# Controller_Schematic.net
KiCad netlist of a schematic drawn in Altium Designer
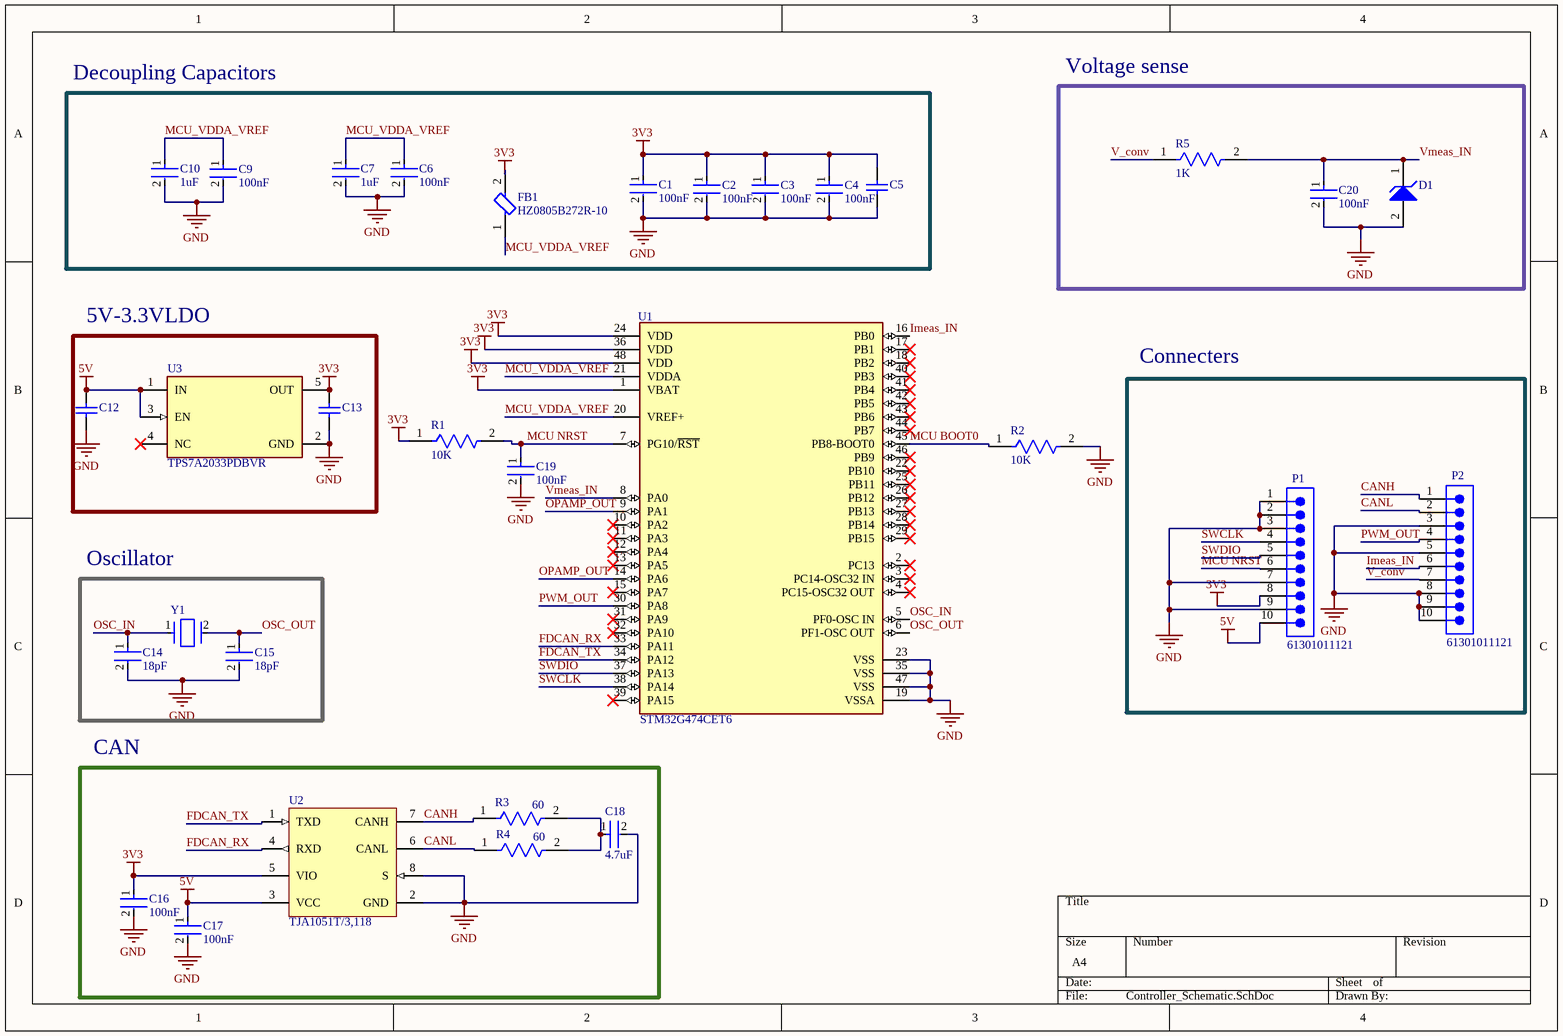
[diagram p0: Controller_Schematic.SchDoc]

(export (version "E")
  (design (tool "Eeschema 10.0.6"))
  (components
    (comp (ref "C1")
      (value "100nF")
      (footprint "FP-GCM21B-0_15-MFG")
      (description "Ceramic Capacitor for Automotive 100nF ±10% 100VDC X7R 0805 Embossed T/R")
      (fields (field (name "TOLERANCE") "10%") (field (name "VOLTAGE") "100V"))
      (libsource (lib "Altium Content Vault") (part "02cd4be3c70576c341d710602a673aa"))
    )
    (comp (ref "C2")
      (value "100nF")
      (footprint "FP-GCM21B-0_15-MFG")
      (description "Ceramic Capacitor for Automotive 100nF ±10% 100VDC X7R 0805 Embossed T/R")
      (fields (field (name "TOLERANCE") "10%") (field (name "VOLTAGE") "100V"))
      (libsource (lib "Altium Content Vault") (part "02cd4be3c70576c341d710602a673aa"))
    )
    (comp (ref "C3")
      (value "100nF")
      (footprint "FP-GCM21B-0_15-MFG")
      (description "Ceramic Capacitor for Automotive 100nF ±10% 100VDC X7R 0805 Embossed T/R")
      (fields (field (name "TOLERANCE") "10%") (field (name "VOLTAGE") "100V"))
      (libsource (lib "Altium Content Vault") (part "02cd4be3c70576c341d710602a673aa"))
    )
    (comp (ref "C4")
      (value "100nF")
      (footprint "FP-GCM21B-0_15-MFG")
      (description "Ceramic Capacitor for Automotive 100nF ±10% 100VDC X7R 0805 Embossed T/R")
      (fields (field (name "TOLERANCE") "10%") (field (name "VOLTAGE") "100V"))
      (libsource (lib "Altium Content Vault") (part "02cd4be3c70576c341d710602a673aa"))
    )
    (comp (ref "C5")
      (value "GRM21BR61A475KA73L")
      (footprint "CAPC2013X140X45NL15T25")
      (fields (field (name "MANUFACTURER") "Murata"))
      (libsource (lib "Altium Content Vault") (part "CAP"))
    )
    (comp (ref "C6")
      (value "100nF")
      (footprint "FP-GCM21B-0_15-MFG")
      (description "Ceramic Capacitor for Automotive 100nF ±10% 100VDC X7R 0805 Embossed T/R")
      (fields (field (name "TOLERANCE") "10%") (field (name "VOLTAGE") "100V"))
      (libsource (lib "Altium Content Vault") (part "02cd4be3c70576c341d710602a673aa"))
    )
    (comp (ref "C7")
      (value "1uF")
      (footprint "FP-GCM21B-0_15-MFG")
      (description "Ceramic Capacitor for Automotive 1uF ±10% 25VDC X7R 0805 Embossed T/R")
      (fields (field (name "TOLERANCE") "10%") (field (name "VOLTAGE") "25V"))
      (libsource (lib "Altium Content Vault") (part "02cd4be3c70576c341d710602a673aa"))
    )
    (comp (ref "C9")
      (value "100nF")
      (footprint "FP-GCM21B-0_15-MFG")
      (description "Ceramic Capacitor for Automotive 100nF ±10% 100VDC X7R 0805 Embossed T/R")
      (fields (field (name "TOLERANCE") "10%") (field (name "VOLTAGE") "100V"))
      (libsource (lib "Altium Content Vault") (part "02cd4be3c70576c341d710602a673aa"))
    )
    (comp (ref "C10")
      (value "1uF")
      (footprint "FP-GCM21B-0_15-MFG")
      (description "Ceramic Capacitor for Automotive 1uF ±10% 25VDC X7R 0805 Embossed T/R")
      (fields (field (name "TOLERANCE") "10%") (field (name "VOLTAGE") "25V"))
      (libsource (lib "Altium Content Vault") (part "02cd4be3c70576c341d710602a673aa"))
    )
    (comp (ref "C12")
      (value "GRM21BR61A106KE19L")
      (footprint "MURA-0805_H_1.35_M")
      (description "CAP, Ceramic, 10 uF, 10%, 10 V, 0805, RoHS, Tape and Reel")
      (fields (field (name "MANUFACTURER") "Murata") (field (name "TOLERANCE") "±10%"))
      (libsource (lib "Altium Content Vault") (part "CAP-NP-2"))
    )
    (comp (ref "C13")
      (value "GRM21BR61A106KE19L")
      (footprint "MURA-0805_H_1.35_M")
      (description "CAP, Ceramic, 10 uF, 10%, 10 V, 0805, RoHS, Tape and Reel")
      (fields (field (name "MANUFACTURER") "Murata") (field (name "TOLERANCE") "±10%"))
      (libsource (lib "Altium Content Vault") (part "CAP-NP-2"))
    )
    (comp (ref "C14")
      (value "18pF")
      (footprint "FP-GRM21A-0_2-IPC_B")
      (description "Chip Multilayer Ceramic Capacitors for General Purpose, 0805, 18pF, C0G, 30ppm/°C, 5%, 200V")
      (fields (field (name "VOLTAGE") "200V") (field (name "TOLERANCE") "5%"))
      (libsource (lib "Altium Content Vault") (part "02cd4be3c70576c341d710602a673aa"))
    )
    (comp (ref "C15")
      (value "18pF")
      (footprint "FP-GRM21A-0_2-IPC_B")
      (description "Chip Multilayer Ceramic Capacitors for General Purpose, 0805, 18pF, C0G, 30ppm/°C, 5%, 200V")
      (fields (field (name "VOLTAGE") "200V") (field (name "TOLERANCE") "5%"))
      (libsource (lib "Altium Content Vault") (part "02cd4be3c70576c341d710602a673aa"))
    )
    (comp (ref "C16")
      (value "100nF")
      (footprint "FP-GCM21B-0_15-MFG")
      (description "Ceramic Capacitor for Automotive 100nF ±10% 100VDC X7R 0805 Embossed T/R")
      (fields (field (name "TOLERANCE") "10%") (field (name "VOLTAGE") "100V"))
      (libsource (lib "Altium Content Vault") (part "02cd4be3c70576c341d710602a673aa"))
    )
    (comp (ref "C17")
      (value "100nF")
      (footprint "FP-GCM21B-0_15-MFG")
      (description "Ceramic Capacitor for Automotive 100nF ±10% 100VDC X7R 0805 Embossed T/R")
      (fields (field (name "TOLERANCE") "10%") (field (name "VOLTAGE") "100V"))
      (libsource (lib "Altium Content Vault") (part "02cd4be3c70576c341d710602a673aa"))
    )
    (comp (ref "C18")
      (value "4.7uF")
      (footprint "FP-GCM21B-0_2-e0_3_0_75-IPC_C")
      (description "Ceramic Capacitor for Automotive 4.7nF ±1% 250VDC C0G 0805 Embossed T/R")
      (libsource (lib "Altium Content Vault") (part "11868f565c42a9108669ba33697ecf6"))
    )
    (comp (ref "C19")
      (value "100nF")
      (footprint "FP-GCM21B-0_15-MFG")
      (description "Ceramic Capacitor for Automotive 100nF ±10% 100VDC X7R 0805 Embossed T/R")
      (fields (field (name "TOLERANCE") "10%") (field (name "VOLTAGE") "100V"))
      (libsource (lib "Altium Content Vault") (part "02cd4be3c70576c341d710602a673aa"))
    )
    (comp (ref "C20")
      (value "100nF")
      (footprint "FP-GCM21B-0_15-MFG")
      (description "Ceramic Capacitor for Automotive 100nF ±10% 100VDC X7R 0805 Embossed T/R")
      (fields (field (name "TOLERANCE") "10%") (field (name "VOLTAGE") "100V"))
      (libsource (lib "Altium Content Vault") (part "02cd4be3c70576c341d710602a673aa"))
    )
    (comp (ref "D1")
      (value "MMSZ5226CT1G")
      (footprint "ONSC-SOD-123-2-425-04_V")
      (description "Zener Voltage Regulator, 500 mW, 2-Pin SOD-123, Pb-Free, Tape and Reel")
      (fields (field (name "MANUFACTURER") "On Semiconductor"))
      (libsource (lib "Altium Content Vault") (part "ONSC-K1A2-2"))
    )
    (comp (ref "FB1")
      (value "HZ0805B272R-10")
      (footprint "FP-HZ0805B272R-10-MFG")
      (description "FERRITE BEAD 2.7 KOHM 0805 1LN")
      (libsource (lib "Altium Content Vault") (part "5f30dd21d616792df468990f7003faa"))
    )
    (comp (ref "P1")
      (value "61301011121")
      (footprint "61301011121")
      (description "THT Vertical Pin Header WR-PHD, Pitch 2.54 mm, Single Row, 10 pins")
      (libsource (lib "Altium Content Vault") (part "Header_Male_1R_10P"))
    )
    (comp (ref "P2")
      (value "61301011121")
      (footprint "61301011121")
      (description "THT Vertical Pin Header WR-PHD, Pitch 2.54 mm, Single Row, 10 pins")
      (libsource (lib "Altium Content Vault") (part "Header_Male_1R_10P"))
    )
    (comp (ref "R1")
      (value "10K")
      (footprint "FP-SR0805-MFG")
      (description "RES SMD 0805 1/2W 1% 10K OHM")
      (fields (field (name "MANUFACTURER PART NUMBER") "SR0805FR-4710KL") (field (name "TOLERANCE") "0.01"))
      (libsource (lib "Altium Content Vault") (part "1029c3af85768c4190bb7ad29bc67b5"))
    )
    (comp (ref "R2")
      (value "10K")
      (footprint "FP-SR0805-MFG")
      (description "RES SMD 0805 1/2W 1% 10K OHM")
      (fields (field (name "MANUFACTURER PART NUMBER") "SR0805FR-4710KL") (field (name "TOLERANCE") "0.01"))
      (libsource (lib "Altium Content Vault") (part "1029c3af85768c4190bb7ad29bc67b5"))
    )
    (comp (ref "R3")
      (value "60")
      (footprint "FP-AC0805-MFG")
      (fields
        (field (name "MANUFACTURER") "Yageo")
        (field (name "OCTOPART") "https://octopart.com/ac0805fr-0759rl-yageo-91867354")
        (field (name "MANUFACTURER PART NUMBER") "AC0805FR-0759RL")
      )
      (libsource (lib "Altium Content Vault") (part "1029c3af85768c4190bb7ad29bc67b5"))
    )
    (comp (ref "R4")
      (value "60")
      (footprint "FP-AC0805-MFG")
      (fields
        (field (name "MANUFACTURER") "Yageo")
        (field (name "OCTOPART") "https://octopart.com/ac0805fr-0759rl-yageo-91867354")
        (field (name "MANUFACTURER PART NUMBER") "AC0805FR-0759RL")
      )
      (libsource (lib "Altium Content Vault") (part "1029c3af85768c4190bb7ad29bc67b5"))
    )
    (comp (ref "R5")
      (value "1K")
      (footprint "FP-AT0805-IPC_B")
      (description "Thin Film Chip Resistors Automotive Grade 1kΩ 0.5% 50ppm/°C 0805")
      (fields (field (name "TOLERANCE") "0.5%"))
      (libsource (lib "Altium Content Vault") (part "1029c3af85768c4190bb7ad29bc67b5"))
    )
    (comp (ref "U1")
      (value "STM32G474CET6")
      (footprint "FP-STM32G474CET6-MFG")
      (description "MAINSTREAM ARM CORTEX-M4 CORE WI")
      (fields
        (field (name "OCTOPART") "https://octopart.com/stm32g474cet6-stmicroelectronics-99072248")
        (field (name "MANUFACTURER") "STMicroelectronics")
      )
      (libsource (lib "Altium Content Vault") (part "96d063d3108c84c79c2ea684d87d0dc"))
    )
    (comp (ref "U2")
      (value "TJA1051T/3,118")
      (footprint "NXP-SOIC-8_L")
      (description "High-Speed CAN Transceiver, 3 to 5 V, 8-Pin SOIC (SOT96-1), RoHS, Tape and Reel")
      (fields (field (name "MANUFACTURER") "NXP"))
      (libsource (lib "Altium Content Vault") (part "NXP-TJA1051T_3-SOIC-8"))
    )
    (comp (ref "U3")
      (value "TPS7A2033PDBVR")
      (footprint "FP-DBV0005A-MFG")
      (description "IC REG LINEAR 3.3V 300MA SOT23-5")
      (libsource (lib "Altium Content Vault") (part "76aa7ad0ceb1012e0d85aeafc53095f"))
    )
    (comp (ref "Y1")
      (value "ABM3-24.000MHZ-B2-T")
      (footprint "FP-ABM3-MFG")
      (description "Crystal 24MHz ±20ppm 18pF SMD-2 5mm x 3.2mm")
      (fields (field (name "TOLERANCE") "20ppm"))
      (libsource (lib "Altium Content Vault") (part "c23a69dc6c9e2f18f2079038eb95dd1"))
    )
  )
  (nets
    (net (code "1") (name "/CANH") (class "Default")
      (node (ref "P2") (pin "1") (pinfunction "1_1") (pintype "passive"))
      (node (ref "R3") (pin "1") (pinfunction "1_1") (pintype "passive"))
      (node (ref "U2") (pin "7") (pinfunction "CANH_7") (pintype "passive"))
    )
    (net (code "2") (name "/CANL") (class "Default")
      (node (ref "P2") (pin "2") (pinfunction "2_2") (pintype "passive"))
      (node (ref "R4") (pin "1") (pinfunction "1_1") (pintype "passive"))
      (node (ref "U2") (pin "6") (pinfunction "CANL_6") (pintype "passive"))
    )
    (net (code "3") (name "/FDCAN_RX") (class "Default")
      (node (ref "U1") (pin "33") (pinfunction "PA11_33") (pintype "bidirectional"))
      (node (ref "U2") (pin "4") (pinfunction "RXD_4") (pintype "output"))
    )
    (net (code "4") (name "/FDCAN_TX") (class "Default")
      (node (ref "U1") (pin "34") (pinfunction "PA12_34") (pintype "bidirectional"))
      (node (ref "U2") (pin "1") (pinfunction "TXD_1") (pintype "input"))
    )
    (net (code "5") (name "/Imeas_IN") (class "Default")
      (node (ref "P2") (pin "6") (pinfunction "6_6") (pintype "passive"))
      (node (ref "U1") (pin "16") (pinfunction "PB0_16") (pintype "bidirectional"))
    )
    (net (code "6") (name "/MCU BOOT0") (class "Default")
      (node (ref "R2") (pin "1") (pinfunction "1_1") (pintype "passive"))
      (node (ref "U1") (pin "45") (pinfunction "PB8-BOOT0_45") (pintype "bidirectional"))
    )
    (net (code "7") (name "/MCU NRST") (class "Default")
      (node (ref "C19") (pin "1") (pinfunction "1_1") (pintype "passive"))
      (node (ref "P1") (pin "6") (pinfunction "6_6") (pintype "passive"))
      (node (ref "R1") (pin "2") (pinfunction "2_2") (pintype "passive"))
      (node (ref "U1") (pin "7") (pinfunction "PG10/~{RST}_7") (pintype "bidirectional"))
    )
    (net (code "8") (name "/MCU_VDDA_VREF") (class "Default")
      (node (ref "C10") (pin "1") (pinfunction "1_1") (pintype "passive"))
      (node (ref "C6") (pin "1") (pinfunction "1_1") (pintype "passive"))
      (node (ref "C7") (pin "1") (pinfunction "1_1") (pintype "passive"))
      (node (ref "C9") (pin "1") (pinfunction "1_1") (pintype "passive"))
      (node (ref "FB1") (pin "1") (pinfunction "1_1") (pintype "passive"))
      (node (ref "U1") (pin "20") (pinfunction "VREF+_20") (pintype "power_in"))
      (node (ref "U1") (pin "21") (pinfunction "VDDA_21") (pintype "power_in"))
    )
    (net (code "9") (name "/OPAMP_OUT") (class "Default")
      (node (ref "U1") (pin "14") (pinfunction "PA6_14") (pintype "bidirectional"))
      (node (ref "U1") (pin "9") (pinfunction "PA1_9") (pintype "bidirectional"))
    )
    (net (code "10") (name "/OSC_IN") (class "Default")
      (node (ref "C14") (pin "1") (pinfunction "1_1") (pintype "passive"))
      (node (ref "U1") (pin "5") (pinfunction "PF0-OSC_IN_5") (pintype "bidirectional"))
      (node (ref "Y1") (pin "1") (pinfunction "1_1") (pintype "passive"))
    )
    (net (code "11") (name "/OSC_OUT") (class "Default")
      (node (ref "C15") (pin "1") (pinfunction "1_1") (pintype "passive"))
      (node (ref "U1") (pin "6") (pinfunction "PF1-OSC_OUT_6") (pintype "bidirectional"))
      (node (ref "Y1") (pin "2") (pinfunction "2_2") (pintype "passive"))
    )
    (net (code "12") (name "/PWM_OUT") (class "Default")
      (node (ref "P2") (pin "4") (pinfunction "4_4") (pintype "passive"))
      (node (ref "U1") (pin "30") (pinfunction "PA8_30") (pintype "bidirectional"))
    )
    (net (code "13") (name "/SWCLK") (class "Default")
      (node (ref "P1") (pin "4") (pinfunction "4_4") (pintype "passive"))
      (node (ref "U1") (pin "38") (pinfunction "PA14_38") (pintype "bidirectional"))
    )
    (net (code "14") (name "/SWDIO") (class "Default")
      (node (ref "P1") (pin "5") (pinfunction "5_5") (pintype "passive"))
      (node (ref "U1") (pin "37") (pinfunction "PA13_37") (pintype "bidirectional"))
    )
    (net (code "15") (name "/V_conv") (class "Default")
      (node (ref "P2") (pin "7") (pinfunction "7_7") (pintype "passive"))
      (node (ref "R5") (pin "1") (pinfunction "1_1") (pintype "passive"))
    )
    (net (code "16") (name "/Vmeas_IN") (class "Default")
      (node (ref "C20") (pin "1") (pinfunction "1_1") (pintype "passive"))
      (node (ref "D1") (pin "1") (pinfunction "K_1") (pintype "passive"))
      (node (ref "R5") (pin "2") (pinfunction "2_2") (pintype "passive"))
      (node (ref "U1") (pin "8") (pinfunction "PA0_8") (pintype "bidirectional"))
    )
    (net (code "17") (name "3V3") (class "Default")
      (node (ref "C1") (pin "1") (pinfunction "1_1") (pintype "passive"))
      (node (ref "C13") (pin "2") (pinfunction "2_2") (pintype "passive"))
      (node (ref "C16") (pin "1") (pinfunction "1_1") (pintype "passive"))
      (node (ref "C2") (pin "1") (pinfunction "1_1") (pintype "passive"))
      (node (ref "C3") (pin "1") (pinfunction "1_1") (pintype "passive"))
      (node (ref "C4") (pin "1") (pinfunction "1_1") (pintype "passive"))
      (node (ref "C5") (pin "2") (pinfunction "2_2") (pintype "passive"))
      (node (ref "FB1") (pin "2") (pinfunction "2_2") (pintype "passive"))
      (node (ref "P1") (pin "8") (pinfunction "8_8") (pintype "passive"))
      (node (ref "R1") (pin "1") (pinfunction "1_1") (pintype "passive"))
      (node (ref "U1") (pin "1") (pinfunction "VBAT_1") (pintype "power_in"))
      (node (ref "U1") (pin "24") (pinfunction "VDD_24") (pintype "power_in"))
      (node (ref "U1") (pin "36") (pinfunction "VDD_36") (pintype "power_in"))
      (node (ref "U1") (pin "48") (pinfunction "VDD_48") (pintype "power_in"))
      (node (ref "U2") (pin "5") (pinfunction "VIO_5") (pintype "power_in"))
      (node (ref "U3") (pin "5") (pinfunction "OUT_5") (pintype "passive"))
    )
    (net (code "18") (name "5V") (class "Default")
      (node (ref "C12") (pin "2") (pinfunction "2_2") (pintype "passive"))
      (node (ref "C17") (pin "1") (pinfunction "1_1") (pintype "passive"))
      (node (ref "P1") (pin "10") (pinfunction "10_10") (pintype "passive"))
      (node (ref "U2") (pin "3") (pinfunction "VCC_3") (pintype "power_in"))
      (node (ref "U3") (pin "1") (pinfunction "IN_1") (pintype "power_in"))
      (node (ref "U3") (pin "3") (pinfunction "EN_3") (pintype "input"))
    )
    (net (code "19") (name "GND") (class "Default")
      (node (ref "C1") (pin "2") (pinfunction "2_2") (pintype "passive"))
      (node (ref "C10") (pin "2") (pinfunction "2_2") (pintype "passive"))
      (node (ref "C12") (pin "1") (pinfunction "1_1") (pintype "passive"))
      (node (ref "C13") (pin "1") (pinfunction "1_1") (pintype "passive"))
      (node (ref "C14") (pin "2") (pinfunction "2_2") (pintype "passive"))
      (node (ref "C15") (pin "2") (pinfunction "2_2") (pintype "passive"))
      (node (ref "C16") (pin "2") (pinfunction "2_2") (pintype "passive"))
      (node (ref "C17") (pin "2") (pinfunction "2_2") (pintype "passive"))
      (node (ref "C18") (pin "2") (pinfunction "2_2") (pintype "passive"))
      (node (ref "C19") (pin "2") (pinfunction "2_2") (pintype "passive"))
      (node (ref "C2") (pin "2") (pinfunction "2_2") (pintype "passive"))
      (node (ref "C20") (pin "2") (pinfunction "2_2") (pintype "passive"))
      (node (ref "C3") (pin "2") (pinfunction "2_2") (pintype "passive"))
      (node (ref "C4") (pin "2") (pinfunction "2_2") (pintype "passive"))
      (node (ref "C5") (pin "1") (pinfunction "1_1") (pintype "passive"))
      (node (ref "C6") (pin "2") (pinfunction "2_2") (pintype "passive"))
      (node (ref "C7") (pin "2") (pinfunction "2_2") (pintype "passive"))
      (node (ref "C9") (pin "2") (pinfunction "2_2") (pintype "passive"))
      (node (ref "D1") (pin "2") (pinfunction "A_2") (pintype "passive"))
      (node (ref "P1") (pin "1") (pinfunction "1_1") (pintype "passive"))
      (node (ref "P1") (pin "2") (pinfunction "2_2") (pintype "passive"))
      (node (ref "P1") (pin "3") (pinfunction "3_3") (pintype "passive"))
      (node (ref "P1") (pin "7") (pinfunction "7_7") (pintype "passive"))
      (node (ref "P1") (pin "9") (pinfunction "9_9") (pintype "passive"))
      (node (ref "P2") (pin "10") (pinfunction "10_10") (pintype "passive"))
      (node (ref "P2") (pin "3") (pinfunction "3_3") (pintype "passive"))
      (node (ref "P2") (pin "5") (pinfunction "5_5") (pintype "passive"))
      (node (ref "P2") (pin "8") (pinfunction "8_8") (pintype "passive"))
      (node (ref "P2") (pin "9") (pinfunction "9_9") (pintype "passive"))
      (node (ref "R2") (pin "2") (pinfunction "2_2") (pintype "passive"))
      (node (ref "U1") (pin "19") (pinfunction "VSSA_19") (pintype "power_in"))
      (node (ref "U1") (pin "23") (pinfunction "VSS_23") (pintype "power_in"))
      (node (ref "U1") (pin "35") (pinfunction "VSS_35") (pintype "power_in"))
      (node (ref "U1") (pin "47") (pinfunction "VSS_47") (pintype "power_in"))
      (node (ref "U2") (pin "2") (pinfunction "GND_2") (pintype "power_in"))
      (node (ref "U2") (pin "8") (pinfunction "S_8") (pintype "input"))
      (node (ref "U3") (pin "2") (pinfunction "GND_2") (pintype "power_in"))
    )
    (net (code "20") (name "Net-(C18-Pad1)") (class "Default")
      (node (ref "C18") (pin "1") (pinfunction "1_1") (pintype "passive"))
      (node (ref "R3") (pin "2") (pinfunction "2_2") (pintype "passive"))
      (node (ref "R4") (pin "2") (pinfunction "2_2") (pintype "passive"))
    )
    (net (code "21") (name "unconnected-(U1-PA2-Pad10)") (class "Default")
      (node (ref "U1") (pin "10") (pinfunction "PA2_10") (pintype "bidirectional+no_connect"))
    )
    (net (code "22") (name "unconnected-(U1-PA3-Pad11)") (class "Default")
      (node (ref "U1") (pin "11") (pinfunction "PA3_11") (pintype "bidirectional+no_connect"))
    )
    (net (code "23") (name "unconnected-(U1-PA4-Pad12)") (class "Default")
      (node (ref "U1") (pin "12") (pinfunction "PA4_12") (pintype "bidirectional+no_connect"))
    )
    (net (code "24") (name "unconnected-(U1-PA5-Pad13)") (class "Default")
      (node (ref "U1") (pin "13") (pinfunction "PA5_13") (pintype "bidirectional+no_connect"))
    )
    (net (code "25") (name "unconnected-(U1-PA7-Pad15)") (class "Default")
      (node (ref "U1") (pin "15") (pinfunction "PA7_15") (pintype "bidirectional+no_connect"))
    )
    (net (code "26") (name "unconnected-(U1-PA9-Pad31)") (class "Default")
      (node (ref "U1") (pin "31") (pinfunction "PA9_31") (pintype "bidirectional+no_connect"))
    )
    (net (code "27") (name "unconnected-(U1-PA10-Pad32)") (class "Default")
      (node (ref "U1") (pin "32") (pinfunction "PA10_32") (pintype "bidirectional+no_connect"))
    )
    (net (code "28") (name "unconnected-(U1-PA15-Pad39)") (class "Default")
      (node (ref "U1") (pin "39") (pinfunction "PA15_39") (pintype "bidirectional+no_connect"))
    )
    (net (code "29") (name "unconnected-(U1-PB1-Pad17)") (class "Default")
      (node (ref "U1") (pin "17") (pinfunction "PB1_17") (pintype "bidirectional+no_connect"))
    )
    (net (code "30") (name "unconnected-(U1-PB2-Pad18)") (class "Default")
      (node (ref "U1") (pin "18") (pinfunction "PB2_18") (pintype "bidirectional+no_connect"))
    )
    (net (code "31") (name "unconnected-(U1-PB3-Pad40)") (class "Default")
      (node (ref "U1") (pin "40") (pinfunction "PB3_40") (pintype "bidirectional+no_connect"))
    )
    (net (code "32") (name "unconnected-(U1-PB4-Pad41)") (class "Default")
      (node (ref "U1") (pin "41") (pinfunction "PB4_41") (pintype "bidirectional+no_connect"))
    )
    (net (code "33") (name "unconnected-(U1-PB5-Pad42)") (class "Default")
      (node (ref "U1") (pin "42") (pinfunction "PB5_42") (pintype "bidirectional+no_connect"))
    )
    (net (code "34") (name "unconnected-(U1-PB6-Pad43)") (class "Default")
      (node (ref "U1") (pin "43") (pinfunction "PB6_43") (pintype "bidirectional+no_connect"))
    )
    (net (code "35") (name "unconnected-(U1-PB7-Pad44)") (class "Default")
      (node (ref "U1") (pin "44") (pinfunction "PB7_44") (pintype "bidirectional+no_connect"))
    )
    (net (code "36") (name "unconnected-(U1-PB9-Pad46)") (class "Default")
      (node (ref "U1") (pin "46") (pinfunction "PB9_46") (pintype "bidirectional+no_connect"))
    )
    (net (code "37") (name "unconnected-(U1-PB10-Pad22)") (class "Default")
      (node (ref "U1") (pin "22") (pinfunction "PB10_22") (pintype "bidirectional+no_connect"))
    )
    (net (code "38") (name "unconnected-(U1-PB11-Pad25)") (class "Default")
      (node (ref "U1") (pin "25") (pinfunction "PB11_25") (pintype "bidirectional+no_connect"))
    )
    (net (code "39") (name "unconnected-(U1-PB12-Pad26)") (class "Default")
      (node (ref "U1") (pin "26") (pinfunction "PB12_26") (pintype "bidirectional+no_connect"))
    )
    (net (code "40") (name "unconnected-(U1-PB13-Pad27)") (class "Default")
      (node (ref "U1") (pin "27") (pinfunction "PB13_27") (pintype "bidirectional+no_connect"))
    )
    (net (code "41") (name "unconnected-(U1-PB14-Pad28)") (class "Default")
      (node (ref "U1") (pin "28") (pinfunction "PB14_28") (pintype "bidirectional+no_connect"))
    )
    (net (code "42") (name "unconnected-(U1-PB15-Pad29)") (class "Default")
      (node (ref "U1") (pin "29") (pinfunction "PB15_29") (pintype "bidirectional+no_connect"))
    )
    (net (code "43") (name "unconnected-(U1-PC13-Pad2)") (class "Default")
      (node (ref "U1") (pin "2") (pinfunction "PC13_2") (pintype "bidirectional+no_connect"))
    )
    (net (code "44") (name "unconnected-(U1-PC14-OSC32_IN-Pad3)") (class "Default")
      (node (ref "U1") (pin "3") (pinfunction "PC14-OSC32_IN_3") (pintype "bidirectional+no_connect"))
    )
    (net (code "45") (name "unconnected-(U1-PC15-OSC32_OUT-Pad4)") (class "Default")
      (node (ref "U1") (pin "4") (pinfunction "PC15-OSC32_OUT_4") (pintype "bidirectional+no_connect"))
    )
    (net (code "46") (name "unconnected-(U3-NC-Pad4)") (class "Default")
      (node (ref "U3") (pin "4") (pinfunction "NC_4") (pintype "passive+no_connect"))
    )
  )
)
